# mother_board_PLA_4.net
KiCad netlist of a schematic drawn in EAGLE
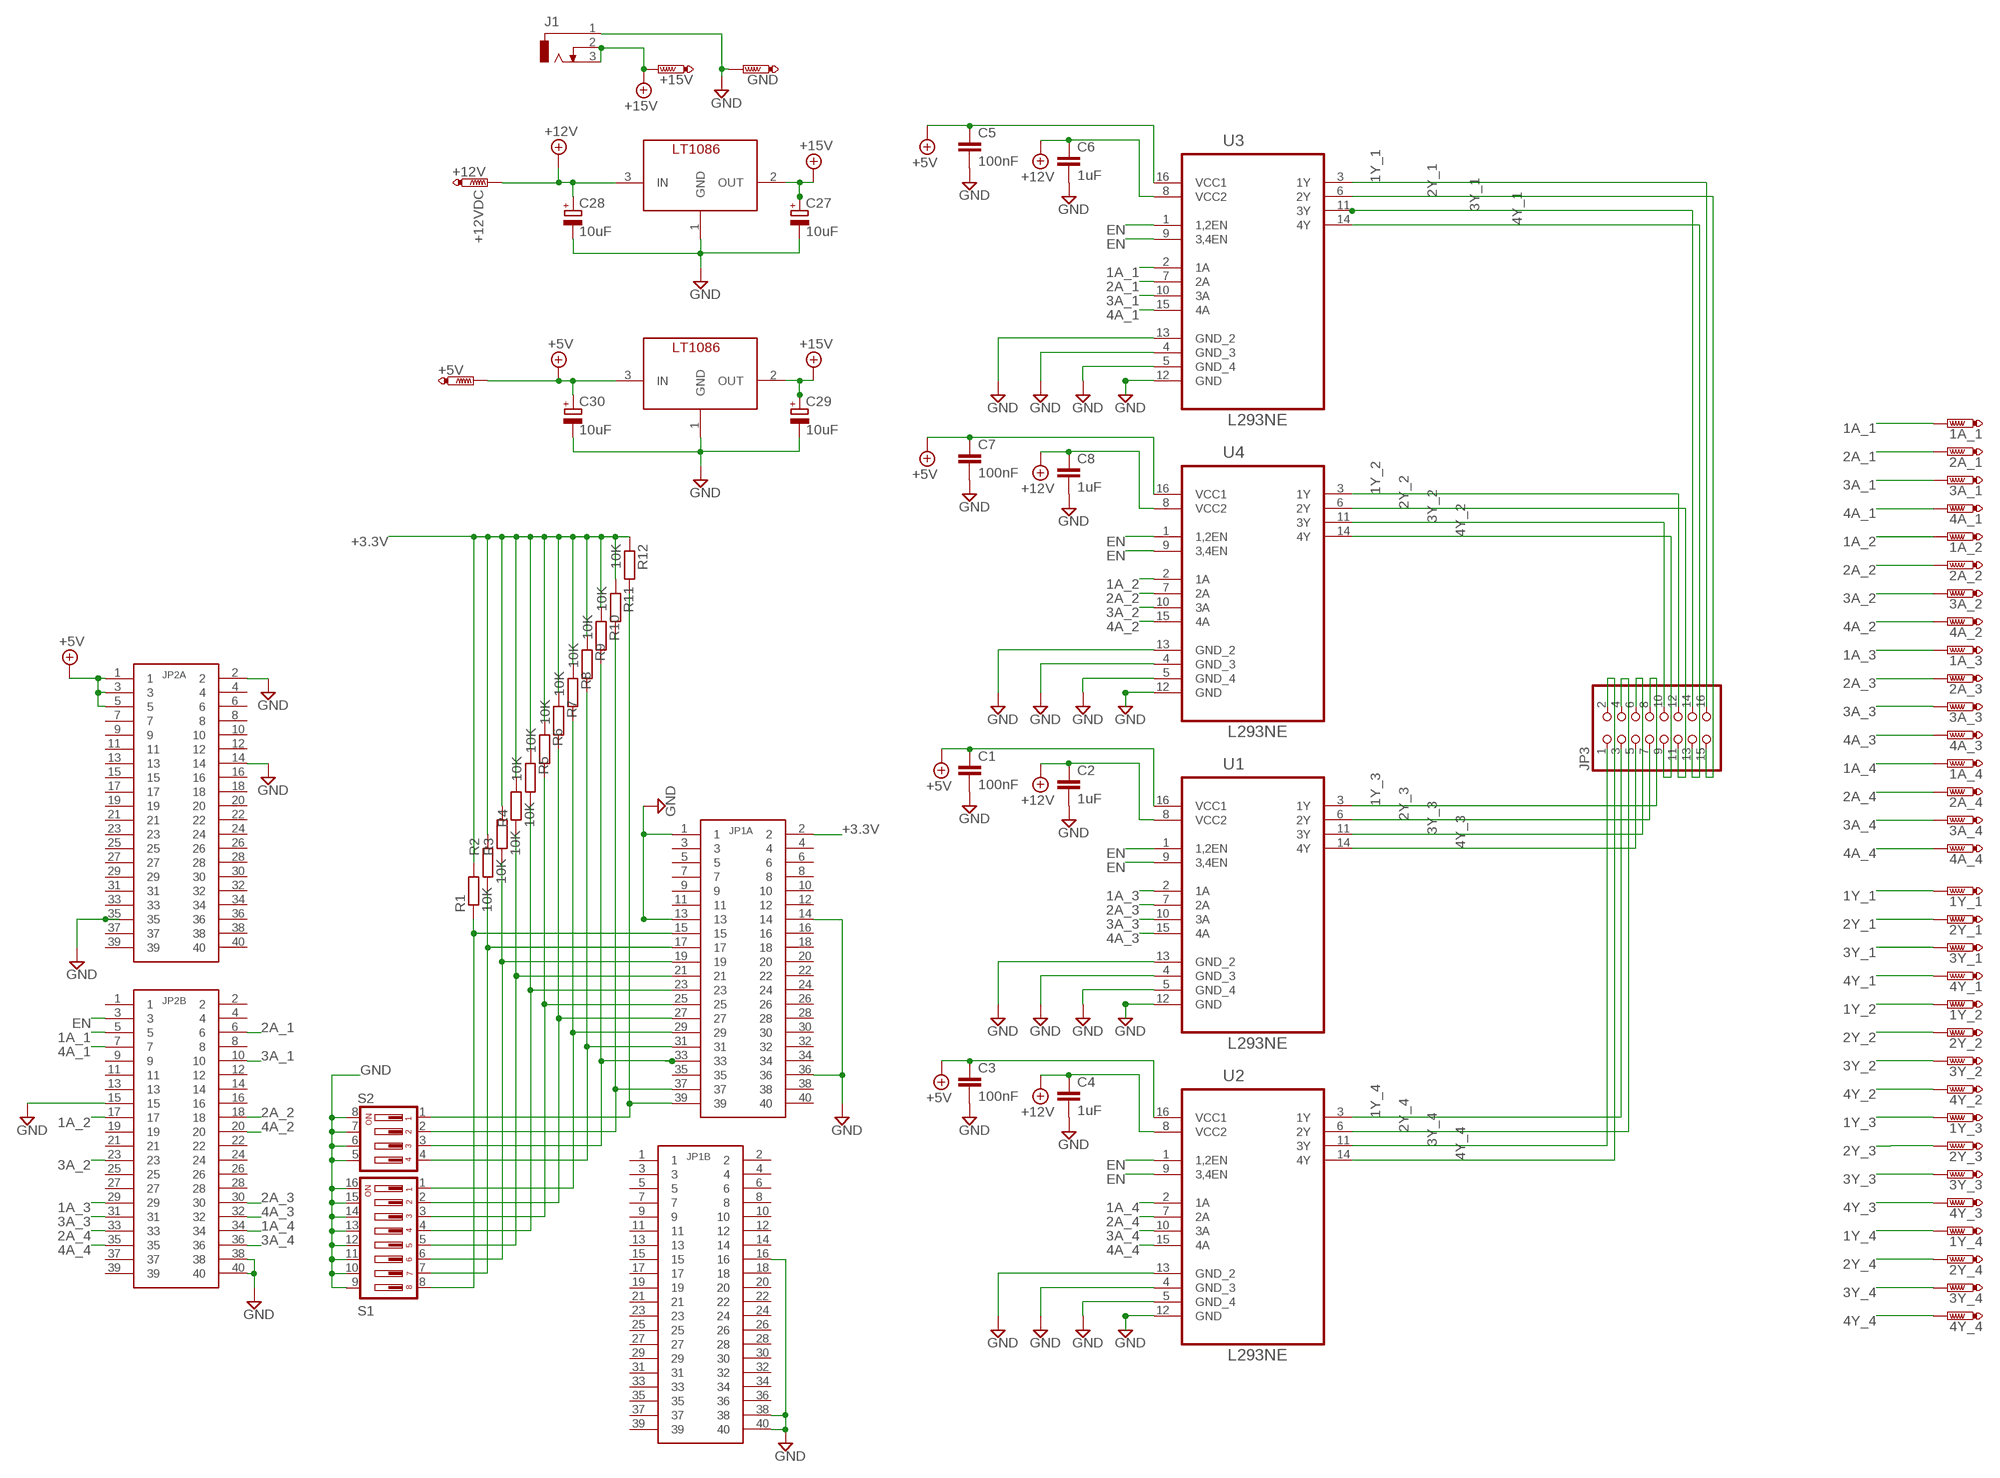
[diagram p0: schematic, sheet 1]

(export (version "E")
  (design (tool "Eeschema 10.0.6"))
  (components
    (comp (ref "+5V")
      (value "PTR1PAD1-20Y")
      (footprint "eagle-import:P1-20Y")
      (fields (field (name "SPICEPREFIX") "X"))
      (libsource (lib "eagle-import") (part "PTR1PAD1-20Y"))
    )
    (comp (ref "+12V")
      (value "PTR1PAD1-20Y")
      (footprint "eagle-import:P1-20Y")
      (fields (field (name "SPICEPREFIX") "X") (field (name "TP_SIGNAL_NAME") "+12VDC"))
      (libsource (lib "eagle-import") (part "PTR1PAD1-20Y"))
    )
    (comp (ref "+15V")
      (value "PTR1PAD1-20Y")
      (footprint "eagle-import:P1-20Y")
      (fields (field (name "SPICEPREFIX") "X"))
      (libsource (lib "eagle-import") (part "PTR1PAD1-20Y"))
    )
    (comp (ref "1A_1")
      (value "PTR1PAD1-20Y")
      (footprint "eagle-import:P1-20Y")
      (fields (field (name "SPICEPREFIX") "X"))
      (libsource (lib "eagle-import") (part "PTR1PAD1-20Y"))
    )
    (comp (ref "1A_2")
      (value "PTR1PAD1-20Y")
      (footprint "eagle-import:P1-20Y")
      (fields (field (name "SPICEPREFIX") "X"))
      (libsource (lib "eagle-import") (part "PTR1PAD1-20Y"))
    )
    (comp (ref "1A_3")
      (value "PTR1PAD1-20Y")
      (footprint "eagle-import:P1-20Y")
      (fields (field (name "SPICEPREFIX") "X"))
      (libsource (lib "eagle-import") (part "PTR1PAD1-20Y"))
    )
    (comp (ref "1A_4")
      (value "PTR1PAD1-20Y")
      (footprint "eagle-import:P1-20Y")
      (fields (field (name "SPICEPREFIX") "X"))
      (libsource (lib "eagle-import") (part "PTR1PAD1-20Y"))
    )
    (comp (ref "1Y_1")
      (value "PTR1PAD1-20Y")
      (footprint "eagle-import:P1-20Y")
      (fields (field (name "SPICEPREFIX") "X"))
      (libsource (lib "eagle-import") (part "PTR1PAD1-20Y"))
    )
    (comp (ref "1Y_2")
      (value "PTR1PAD1-20Y")
      (footprint "eagle-import:P1-20Y")
      (fields (field (name "SPICEPREFIX") "X"))
      (libsource (lib "eagle-import") (part "PTR1PAD1-20Y"))
    )
    (comp (ref "1Y_3")
      (value "PTR1PAD1-20Y")
      (footprint "eagle-import:P1-20Y")
      (fields (field (name "SPICEPREFIX") "X"))
      (libsource (lib "eagle-import") (part "PTR1PAD1-20Y"))
    )
    (comp (ref "1Y_4")
      (value "PTR1PAD1-20Y")
      (footprint "eagle-import:P1-20Y")
      (fields (field (name "SPICEPREFIX") "X"))
      (libsource (lib "eagle-import") (part "PTR1PAD1-20Y"))
    )
    (comp (ref "2A_1")
      (value "PTR1PAD1-20Y")
      (footprint "eagle-import:P1-20Y")
      (fields (field (name "SPICEPREFIX") "X"))
      (libsource (lib "eagle-import") (part "PTR1PAD1-20Y"))
    )
    (comp (ref "2A_2")
      (value "PTR1PAD1-20Y")
      (footprint "eagle-import:P1-20Y")
      (fields (field (name "SPICEPREFIX") "X"))
      (libsource (lib "eagle-import") (part "PTR1PAD1-20Y"))
    )
    (comp (ref "2A_3")
      (value "PTR1PAD1-20Y")
      (footprint "eagle-import:P1-20Y")
      (fields (field (name "SPICEPREFIX") "X"))
      (libsource (lib "eagle-import") (part "PTR1PAD1-20Y"))
    )
    (comp (ref "2A_4")
      (value "PTR1PAD1-20Y")
      (footprint "eagle-import:P1-20Y")
      (fields (field (name "SPICEPREFIX") "X"))
      (libsource (lib "eagle-import") (part "PTR1PAD1-20Y"))
    )
    (comp (ref "2Y_1")
      (value "PTR1PAD1-20Y")
      (footprint "eagle-import:P1-20Y")
      (fields (field (name "SPICEPREFIX") "X"))
      (libsource (lib "eagle-import") (part "PTR1PAD1-20Y"))
    )
    (comp (ref "2Y_2")
      (value "PTR1PAD1-20Y")
      (footprint "eagle-import:P1-20Y")
      (fields (field (name "SPICEPREFIX") "X"))
      (libsource (lib "eagle-import") (part "PTR1PAD1-20Y"))
    )
    (comp (ref "2Y_3")
      (value "PTR1PAD1-20Y")
      (footprint "eagle-import:P1-20Y")
      (fields (field (name "SPICEPREFIX") "X"))
      (libsource (lib "eagle-import") (part "PTR1PAD1-20Y"))
    )
    (comp (ref "2Y_4")
      (value "PTR1PAD1-20Y")
      (footprint "eagle-import:P1-20Y")
      (fields (field (name "SPICEPREFIX") "X"))
      (libsource (lib "eagle-import") (part "PTR1PAD1-20Y"))
    )
    (comp (ref "3A_1")
      (value "PTR1PAD1-20Y")
      (footprint "eagle-import:P1-20Y")
      (fields (field (name "SPICEPREFIX") "X"))
      (libsource (lib "eagle-import") (part "PTR1PAD1-20Y"))
    )
    (comp (ref "3A_2")
      (value "PTR1PAD1-20Y")
      (footprint "eagle-import:P1-20Y")
      (fields (field (name "SPICEPREFIX") "X"))
      (libsource (lib "eagle-import") (part "PTR1PAD1-20Y"))
    )
    (comp (ref "3A_3")
      (value "PTR1PAD1-20Y")
      (footprint "eagle-import:P1-20Y")
      (fields (field (name "SPICEPREFIX") "X"))
      (libsource (lib "eagle-import") (part "PTR1PAD1-20Y"))
    )
    (comp (ref "3A_4")
      (value "PTR1PAD1-20Y")
      (footprint "eagle-import:P1-20Y")
      (fields (field (name "SPICEPREFIX") "X"))
      (libsource (lib "eagle-import") (part "PTR1PAD1-20Y"))
    )
    (comp (ref "3Y_1")
      (value "PTR1PAD1-20Y")
      (footprint "eagle-import:P1-20Y")
      (fields (field (name "SPICEPREFIX") "X"))
      (libsource (lib "eagle-import") (part "PTR1PAD1-20Y"))
    )
    (comp (ref "3Y_2")
      (value "PTR1PAD1-20Y")
      (footprint "eagle-import:P1-20Y")
      (fields (field (name "SPICEPREFIX") "X"))
      (libsource (lib "eagle-import") (part "PTR1PAD1-20Y"))
    )
    (comp (ref "3Y_3")
      (value "PTR1PAD1-20Y")
      (footprint "eagle-import:P1-20Y")
      (fields (field (name "SPICEPREFIX") "X"))
      (libsource (lib "eagle-import") (part "PTR1PAD1-20Y"))
    )
    (comp (ref "3Y_4")
      (value "PTR1PAD1-20Y")
      (footprint "eagle-import:P1-20Y")
      (fields (field (name "SPICEPREFIX") "X"))
      (libsource (lib "eagle-import") (part "PTR1PAD1-20Y"))
    )
    (comp (ref "4A_1")
      (value "PTR1PAD1-20Y")
      (footprint "eagle-import:P1-20Y")
      (fields (field (name "SPICEPREFIX") "X"))
      (libsource (lib "eagle-import") (part "PTR1PAD1-20Y"))
    )
    (comp (ref "4A_2")
      (value "PTR1PAD1-20Y")
      (footprint "eagle-import:P1-20Y")
      (fields (field (name "SPICEPREFIX") "X"))
      (libsource (lib "eagle-import") (part "PTR1PAD1-20Y"))
    )
    (comp (ref "4A_3")
      (value "PTR1PAD1-20Y")
      (footprint "eagle-import:P1-20Y")
      (fields (field (name "SPICEPREFIX") "X"))
      (libsource (lib "eagle-import") (part "PTR1PAD1-20Y"))
    )
    (comp (ref "4A_4")
      (value "PTR1PAD1-20Y")
      (footprint "eagle-import:P1-20Y")
      (fields (field (name "SPICEPREFIX") "X"))
      (libsource (lib "eagle-import") (part "PTR1PAD1-20Y"))
    )
    (comp (ref "4Y_1")
      (value "PTR1PAD1-20Y")
      (footprint "eagle-import:P1-20Y")
      (fields (field (name "SPICEPREFIX") "X"))
      (libsource (lib "eagle-import") (part "PTR1PAD1-20Y"))
    )
    (comp (ref "4Y_2")
      (value "PTR1PAD1-20Y")
      (footprint "eagle-import:P1-20Y")
      (fields (field (name "SPICEPREFIX") "X"))
      (libsource (lib "eagle-import") (part "PTR1PAD1-20Y"))
    )
    (comp (ref "4Y_3")
      (value "PTR1PAD1-20Y")
      (footprint "eagle-import:P1-20Y")
      (fields (field (name "SPICEPREFIX") "X"))
      (libsource (lib "eagle-import") (part "PTR1PAD1-20Y"))
    )
    (comp (ref "4Y_4")
      (value "PTR1PAD1-20Y")
      (footprint "eagle-import:P1-20Y")
      (fields (field (name "SPICEPREFIX") "X"))
      (libsource (lib "eagle-import") (part "PTR1PAD1-20Y"))
    )
    (comp (ref "C1")
      (value "100nF")
      (footprint "eagle-import:C050-030X075")
      (libsource (lib "eagle-import") (part "C-EU050-030X075"))
    )
    (comp (ref "C2")
      (value "1uF")
      (footprint "eagle-import:C050-030X075")
      (libsource (lib "eagle-import") (part "C-EU050-030X075"))
    )
    (comp (ref "C3")
      (value "100nF")
      (footprint "eagle-import:C050-030X075")
      (libsource (lib "eagle-import") (part "C-EU050-030X075"))
    )
    (comp (ref "C4")
      (value "1uF")
      (footprint "eagle-import:C050-030X075")
      (libsource (lib "eagle-import") (part "C-EU050-030X075"))
    )
    (comp (ref "C5")
      (value "100nF")
      (footprint "eagle-import:C050-030X075")
      (libsource (lib "eagle-import") (part "C-EU050-030X075"))
    )
    (comp (ref "C6")
      (value "1uF")
      (footprint "eagle-import:C050-030X075")
      (libsource (lib "eagle-import") (part "C-EU050-030X075"))
    )
    (comp (ref "C7")
      (value "100nF")
      (footprint "eagle-import:C050-030X075")
      (fields (field (name "SPICEPREFIX") "100n"))
      (libsource (lib "eagle-import") (part "C-EU050-030X075"))
    )
    (comp (ref "C8")
      (value "1uF")
      (footprint "eagle-import:C050-030X075")
      (fields (field (name "SPICEPREFIX") "1uF"))
      (libsource (lib "eagle-import") (part "C-EU050-030X075"))
    )
    (comp (ref "C27")
      (value "10uF")
      (footprint "eagle-import:E5-10,5")
      (libsource (lib "eagle-import") (part "CPOL-EUE5-10.5"))
    )
    (comp (ref "C28")
      (value "10uF")
      (footprint "eagle-import:E5-10,5")
      (libsource (lib "eagle-import") (part "CPOL-EUE5-10.5"))
    )
    (comp (ref "C29")
      (value "10uF")
      (footprint "eagle-import:E5-10,5")
      (libsource (lib "eagle-import") (part "CPOL-EUE5-10.5"))
    )
    (comp (ref "C30")
      (value "10uF")
      (footprint "eagle-import:E5-10,5")
      (libsource (lib "eagle-import") (part "CPOL-EUE5-10.5"))
    )
    (comp (ref "GND")
      (value "PTR1PAD1-20Y")
      (footprint "eagle-import:P1-20Y")
      (fields (field (name "SPICEPREFIX") "X"))
      (libsource (lib "eagle-import") (part "PTR1PAD1-20Y"))
    )
    (comp (ref "J1")
      (value "DCJ0303")
      (footprint "eagle-import:DCJ0303")
      (libsource (lib "eagle-import") (part "DCJ0303"))
    )
    (comp (ref "JP1A")
      (value "PIN_HEADER_2MM")
      (footprint "eagle-import:PIN_HEADER_2MM")
      (libsource (lib "eagle-import") (part "PIN_HEADER_2MM"))
    )
    (comp (ref "JP1B")
      (value "PIN_HEADER_2MM")
      (footprint "eagle-import:PIN_HEADER_2MM")
      (libsource (lib "eagle-import") (part "PIN_HEADER_2MM"))
    )
    (comp (ref "JP2A")
      (value "PIN_HEADER_2MM")
      (footprint "eagle-import:PIN_HEADER_2MM")
      (libsource (lib "eagle-import") (part "PIN_HEADER_2MM"))
    )
    (comp (ref "JP2B")
      (value "PIN_HEADER_2MM")
      (footprint "eagle-import:PIN_HEADER_2MM")
      (libsource (lib "eagle-import") (part "PIN_HEADER_2MM"))
    )
    (comp (ref "JP3")
      (value "PINHD-2X8")
      (footprint "eagle-import:2X08")
      (libsource (lib "eagle-import") (part "PINHD-2X8"))
    )
    (comp (ref "R1")
      (value "10K")
      (footprint "eagle-import:0207_10")
      (libsource (lib "eagle-import") (part "R-EU_0207/10"))
    )
    (comp (ref "R2")
      (value "10K")
      (footprint "eagle-import:0207_10")
      (libsource (lib "eagle-import") (part "R-EU_0207/10"))
    )
    (comp (ref "R3")
      (value "10K")
      (footprint "eagle-import:0207_10")
      (libsource (lib "eagle-import") (part "R-EU_0207/10"))
    )
    (comp (ref "R4")
      (value "10K")
      (footprint "eagle-import:0207_10")
      (libsource (lib "eagle-import") (part "R-EU_0207/10"))
    )
    (comp (ref "R5")
      (value "10K")
      (footprint "eagle-import:0207_10")
      (libsource (lib "eagle-import") (part "R-EU_0207/10"))
    )
    (comp (ref "R6")
      (value "10K")
      (footprint "eagle-import:0207_10")
      (libsource (lib "eagle-import") (part "R-EU_0207/10"))
    )
    (comp (ref "R7")
      (value "10K")
      (footprint "eagle-import:0207_10")
      (libsource (lib "eagle-import") (part "R-EU_0207/10"))
    )
    (comp (ref "R8")
      (value "10K")
      (footprint "eagle-import:0207_10")
      (libsource (lib "eagle-import") (part "R-EU_0207/10"))
    )
    (comp (ref "R9")
      (value "10K")
      (footprint "eagle-import:0207_10")
      (libsource (lib "eagle-import") (part "R-EU_0207/10"))
    )
    (comp (ref "R10")
      (value "10K")
      (footprint "eagle-import:0207_10")
      (libsource (lib "eagle-import") (part "R-EU_0207/10"))
    )
    (comp (ref "R11")
      (value "10K")
      (footprint "eagle-import:0207_10")
      (libsource (lib "eagle-import") (part "R-EU_0207/10"))
    )
    (comp (ref "R12")
      (value "10K")
      (footprint "eagle-import:0207_10")
      (libsource (lib "eagle-import") (part "R-EU_0207/10"))
    )
    (comp (ref "S1")
      (value "DIP04YL")
      (footprint "eagle-import:DIP04YL")
      (libsource (lib "eagle-import") (part "DIP04YL"))
    )
    (comp (ref "S2")
      (value "DIP08YL")
      (footprint "eagle-import:DIP08YL")
      (libsource (lib "eagle-import") (part "DIP08YL"))
    )
    (comp (ref "U$4")
      (value "LT1086LT1086-V")
      (footprint "eagle-import:TO220_VERTICAL")
      (libsource (lib "eagle-import") (part "LT1086LT1086-V"))
    )
    (comp (ref "U$6")
      (value "LT1086LT1086-V")
      (footprint "eagle-import:TO220_VERTICAL")
      (libsource (lib "eagle-import") (part "LT1086LT1086-V"))
    )
    (comp (ref "U1")
      (value "L293NE")
      (footprint "eagle-import:DIP254P762X508-16")
      (libsource (lib "eagle-import") (part "L293NE"))
    )
    (comp (ref "U2")
      (value "L293NE")
      (footprint "eagle-import:DIP254P762X508-16")
      (libsource (lib "eagle-import") (part "L293NE"))
    )
    (comp (ref "U3")
      (value "L293NE")
      (footprint "eagle-import:DIP254P762X508-16")
      (libsource (lib "eagle-import") (part "L293NE"))
    )
    (comp (ref "U4")
      (value "L293NE")
      (footprint "eagle-import:DIP254P762X508-16")
      (libsource (lib "eagle-import") (part "L293NE"))
    )
  )
  (nets
    (net (code "1") (name "+5V") (class "Default")
      (node (ref "+5V") (pin "TP") (pinfunction "TP_TP") (pintype "input"))
      (node (ref "C1") (pin "1") (pinfunction "1_1") (pintype "passive"))
      (node (ref "C3") (pin "1") (pinfunction "1_1") (pintype "passive"))
      (node (ref "C30") (pin "+") (pinfunction "+_+") (pintype "passive"))
      (node (ref "C5") (pin "1") (pinfunction "1_1") (pintype "passive"))
      (node (ref "C7") (pin "1") (pinfunction "1_1") (pintype "passive"))
      (node (ref "JP2A") (pin "1") (pinfunction "1_1") (pintype "bidirectional"))
      (node (ref "JP2A") (pin "3") (pinfunction "3_3") (pintype "bidirectional"))
      (node (ref "JP2A") (pin "5") (pinfunction "5_5") (pintype "bidirectional"))
      (node (ref "U$4") (pin "3") (pinfunction "IN_3") (pintype "bidirectional"))
      (node (ref "U1") (pin "16") (pinfunction "VCC1_16") (pintype "power_in"))
      (node (ref "U2") (pin "16") (pinfunction "VCC1_16") (pintype "power_in"))
      (node (ref "U3") (pin "16") (pinfunction "VCC1_16") (pintype "power_in"))
      (node (ref "U4") (pin "16") (pinfunction "VCC1_16") (pintype "power_in"))
    )
    (net (code "2") (name "+12V") (class "Default")
      (node (ref "+12V") (pin "TP") (pinfunction "TP_TP") (pintype "input"))
      (node (ref "C2") (pin "1") (pinfunction "1_1") (pintype "passive"))
      (node (ref "C28") (pin "+") (pinfunction "+_+") (pintype "passive"))
      (node (ref "C4") (pin "1") (pinfunction "1_1") (pintype "passive"))
      (node (ref "C6") (pin "1") (pinfunction "1_1") (pintype "passive"))
      (node (ref "C8") (pin "1") (pinfunction "1_1") (pintype "passive"))
      (node (ref "U$6") (pin "3") (pinfunction "IN_3") (pintype "bidirectional"))
      (node (ref "U1") (pin "8") (pinfunction "VCC2_8") (pintype "power_in"))
      (node (ref "U2") (pin "8") (pinfunction "VCC2_8") (pintype "power_in"))
      (node (ref "U3") (pin "8") (pinfunction "VCC2_8") (pintype "power_in"))
      (node (ref "U4") (pin "8") (pinfunction "VCC2_8") (pintype "power_in"))
    )
    (net (code "3") (name "+15V") (class "Default")
      (node (ref "+15V") (pin "TP") (pinfunction "TP_TP") (pintype "input"))
      (node (ref "C27") (pin "+") (pinfunction "+_+") (pintype "passive"))
      (node (ref "C29") (pin "+") (pinfunction "+_+") (pintype "passive"))
      (node (ref "J1") (pin "2") (pinfunction "2_2") (pintype "passive"))
      (node (ref "J1") (pin "3") (pinfunction "3_3") (pintype "passive"))
      (node (ref "U$4") (pin "2") (pinfunction "OUT_2") (pintype "bidirectional"))
      (node (ref "U$6") (pin "2") (pinfunction "OUT_2") (pintype "bidirectional"))
    )
    (net (code "4") (name "/+3.3V") (class "Default")
      (node (ref "JP1A") (pin "2") (pinfunction "2_2") (pintype "bidirectional"))
      (node (ref "R1") (pin "2") (pinfunction "2_2") (pintype "passive"))
      (node (ref "R10") (pin "1") (pinfunction "1_1") (pintype "passive"))
      (node (ref "R11") (pin "1") (pinfunction "1_1") (pintype "passive"))
      (node (ref "R12") (pin "1") (pinfunction "1_1") (pintype "passive"))
      (node (ref "R2") (pin "2") (pinfunction "2_2") (pintype "passive"))
      (node (ref "R3") (pin "2") (pinfunction "2_2") (pintype "passive"))
      (node (ref "R4") (pin "2") (pinfunction "2_2") (pintype "passive"))
      (node (ref "R5") (pin "1") (pinfunction "1_1") (pintype "passive"))
      (node (ref "R6") (pin "1") (pinfunction "1_1") (pintype "passive"))
      (node (ref "R7") (pin "1") (pinfunction "1_1") (pintype "passive"))
      (node (ref "R8") (pin "1") (pinfunction "1_1") (pintype "passive"))
      (node (ref "R9") (pin "1") (pinfunction "1_1") (pintype "passive"))
    )
    (net (code "5") (name "/1A_1") (class "Default")
      (node (ref "1A_1") (pin "TP") (pinfunction "TP_TP") (pintype "input"))
      (node (ref "JP2B") (pin "5") (pinfunction "5_5") (pintype "bidirectional"))
      (node (ref "U3") (pin "2") (pinfunction "1A_2") (pintype "input"))
    )
    (net (code "6") (name "/1A_2") (class "Default")
      (node (ref "1A_2") (pin "TP") (pinfunction "TP_TP") (pintype "input"))
      (node (ref "JP2B") (pin "17") (pinfunction "17_17") (pintype "bidirectional"))
      (node (ref "U4") (pin "2") (pinfunction "1A_2") (pintype "input"))
    )
    (net (code "7") (name "/1A_3") (class "Default")
      (node (ref "1A_3") (pin "TP") (pinfunction "TP_TP") (pintype "input"))
      (node (ref "JP2B") (pin "29") (pinfunction "29_29") (pintype "bidirectional"))
      (node (ref "U1") (pin "2") (pinfunction "1A_2") (pintype "input"))
    )
    (net (code "8") (name "/1A_4") (class "Default")
      (node (ref "1A_4") (pin "TP") (pinfunction "TP_TP") (pintype "input"))
      (node (ref "JP2B") (pin "34") (pinfunction "34_34") (pintype "bidirectional"))
      (node (ref "U2") (pin "2") (pinfunction "1A_2") (pintype "input"))
    )
    (net (code "9") (name "/1Y_1") (class "Default")
      (node (ref "1Y_1") (pin "TP") (pinfunction "TP_TP") (pintype "input"))
      (node (ref "JP3") (pin "16") (pinfunction "16_16") (pintype "passive"))
      (node (ref "U3") (pin "3") (pinfunction "1Y_3") (pintype "output"))
    )
    (net (code "10") (name "/1Y_2") (class "Default")
      (node (ref "1Y_2") (pin "TP") (pinfunction "TP_TP") (pintype "input"))
      (node (ref "JP3") (pin "12") (pinfunction "12_12") (pintype "passive"))
      (node (ref "U4") (pin "3") (pinfunction "1Y_3") (pintype "output"))
    )
    (net (code "11") (name "/1Y_3") (class "Default")
      (node (ref "1Y_3") (pin "TP") (pinfunction "TP_TP") (pintype "input"))
      (node (ref "JP3") (pin "8") (pinfunction "8_8") (pintype "passive"))
      (node (ref "U1") (pin "3") (pinfunction "1Y_3") (pintype "output"))
    )
    (net (code "12") (name "/1Y_4") (class "Default")
      (node (ref "1Y_4") (pin "TP") (pinfunction "TP_TP") (pintype "input"))
      (node (ref "JP3") (pin "3") (pinfunction "3_3") (pintype "passive"))
      (node (ref "U2") (pin "3") (pinfunction "1Y_3") (pintype "output"))
    )
    (net (code "13") (name "/2A_1") (class "Default")
      (node (ref "2A_1") (pin "TP") (pinfunction "TP_TP") (pintype "input"))
      (node (ref "JP2B") (pin "6") (pinfunction "6_6") (pintype "bidirectional"))
      (node (ref "U3") (pin "7") (pinfunction "2A_7") (pintype "input"))
    )
    (net (code "14") (name "/2A_2") (class "Default")
      (node (ref "2A_2") (pin "TP") (pinfunction "TP_TP") (pintype "input"))
      (node (ref "JP2B") (pin "18") (pinfunction "18_18") (pintype "bidirectional"))
      (node (ref "U4") (pin "7") (pinfunction "2A_7") (pintype "input"))
    )
    (net (code "15") (name "/2A_3") (class "Default")
      (node (ref "2A_3") (pin "TP") (pinfunction "TP_TP") (pintype "input"))
      (node (ref "JP2B") (pin "30") (pinfunction "30_30") (pintype "bidirectional"))
      (node (ref "U1") (pin "7") (pinfunction "2A_7") (pintype "input"))
    )
    (net (code "16") (name "/2A_4") (class "Default")
      (node (ref "2A_4") (pin "TP") (pinfunction "TP_TP") (pintype "input"))
      (node (ref "JP2B") (pin "33") (pinfunction "33_33") (pintype "bidirectional"))
      (node (ref "U2") (pin "7") (pinfunction "2A_7") (pintype "input"))
    )
    (net (code "17") (name "/2Y_1") (class "Default")
      (node (ref "2Y_1") (pin "TP") (pinfunction "TP_TP") (pintype "input"))
      (node (ref "JP3") (pin "15") (pinfunction "15_15") (pintype "passive"))
      (node (ref "U3") (pin "6") (pinfunction "2Y_6") (pintype "output"))
    )
    (net (code "18") (name "/2Y_2") (class "Default")
      (node (ref "2Y_2") (pin "TP") (pinfunction "TP_TP") (pintype "input"))
      (node (ref "JP3") (pin "11") (pinfunction "11_11") (pintype "passive"))
      (node (ref "U4") (pin "6") (pinfunction "2Y_6") (pintype "output"))
    )
    (net (code "19") (name "/2Y_3") (class "Default")
      (node (ref "2Y_3") (pin "TP") (pinfunction "TP_TP") (pintype "input"))
      (node (ref "JP3") (pin "7") (pinfunction "7_7") (pintype "passive"))
      (node (ref "U1") (pin "6") (pinfunction "2Y_6") (pintype "output"))
    )
    (net (code "20") (name "/2Y_4") (class "Default")
      (node (ref "2Y_4") (pin "TP") (pinfunction "TP_TP") (pintype "input"))
      (node (ref "JP3") (pin "4") (pinfunction "4_4") (pintype "passive"))
      (node (ref "U2") (pin "6") (pinfunction "2Y_6") (pintype "output"))
    )
    (net (code "21") (name "/3A_1") (class "Default")
      (node (ref "3A_1") (pin "TP") (pinfunction "TP_TP") (pintype "input"))
      (node (ref "JP2B") (pin "10") (pinfunction "10_10") (pintype "bidirectional"))
      (node (ref "U3") (pin "10") (pinfunction "3A_10") (pintype "input"))
    )
    (net (code "22") (name "/3A_2") (class "Default")
      (node (ref "3A_2") (pin "TP") (pinfunction "TP_TP") (pintype "input"))
      (node (ref "JP2B") (pin "23") (pinfunction "23_23") (pintype "bidirectional"))
      (node (ref "U4") (pin "10") (pinfunction "3A_10") (pintype "input"))
    )
    (net (code "23") (name "/3A_3") (class "Default")
      (node (ref "3A_3") (pin "TP") (pinfunction "TP_TP") (pintype "input"))
      (node (ref "JP2B") (pin "31") (pinfunction "31_31") (pintype "bidirectional"))
      (node (ref "U1") (pin "10") (pinfunction "3A_10") (pintype "input"))
    )
    (net (code "24") (name "/3A_4") (class "Default")
      (node (ref "3A_4") (pin "TP") (pinfunction "TP_TP") (pintype "input"))
      (node (ref "JP2B") (pin "36") (pinfunction "36_36") (pintype "bidirectional"))
      (node (ref "U2") (pin "10") (pinfunction "3A_10") (pintype "input"))
    )
    (net (code "25") (name "/3Y_1") (class "Default")
      (node (ref "3Y_1") (pin "TP") (pinfunction "TP_TP") (pintype "input"))
      (node (ref "JP3") (pin "14") (pinfunction "14_14") (pintype "passive"))
      (node (ref "U3") (pin "11") (pinfunction "3Y_11") (pintype "output"))
    )
    (net (code "26") (name "/3Y_2") (class "Default")
      (node (ref "3Y_2") (pin "TP") (pinfunction "TP_TP") (pintype "input"))
      (node (ref "JP3") (pin "10") (pinfunction "10_10") (pintype "passive"))
      (node (ref "U4") (pin "11") (pinfunction "3Y_11") (pintype "output"))
    )
    (net (code "27") (name "/3Y_3") (class "Default")
      (node (ref "3Y_3") (pin "TP") (pinfunction "TP_TP") (pintype "input"))
      (node (ref "JP3") (pin "6") (pinfunction "6_6") (pintype "passive"))
      (node (ref "U1") (pin "11") (pinfunction "3Y_11") (pintype "output"))
    )
    (net (code "28") (name "/3Y_4") (class "Default")
      (node (ref "3Y_4") (pin "TP") (pinfunction "TP_TP") (pintype "input"))
      (node (ref "JP3") (pin "1") (pinfunction "1_1") (pintype "passive"))
      (node (ref "U2") (pin "11") (pinfunction "3Y_11") (pintype "output"))
    )
    (net (code "29") (name "/4A_1") (class "Default")
      (node (ref "4A_1") (pin "TP") (pinfunction "TP_TP") (pintype "input"))
      (node (ref "JP2B") (pin "7") (pinfunction "7_7") (pintype "bidirectional"))
      (node (ref "U3") (pin "15") (pinfunction "4A_15") (pintype "input"))
    )
    (net (code "30") (name "/4A_2") (class "Default")
      (node (ref "4A_2") (pin "TP") (pinfunction "TP_TP") (pintype "input"))
      (node (ref "JP2B") (pin "20") (pinfunction "20_20") (pintype "bidirectional"))
      (node (ref "U4") (pin "15") (pinfunction "4A_15") (pintype "input"))
    )
    (net (code "31") (name "/4A_3") (class "Default")
      (node (ref "4A_3") (pin "TP") (pinfunction "TP_TP") (pintype "input"))
      (node (ref "JP2B") (pin "32") (pinfunction "32_32") (pintype "bidirectional"))
      (node (ref "U1") (pin "15") (pinfunction "4A_15") (pintype "input"))
    )
    (net (code "32") (name "/4A_4") (class "Default")
      (node (ref "4A_4") (pin "TP") (pinfunction "TP_TP") (pintype "input"))
      (node (ref "JP2B") (pin "35") (pinfunction "35_35") (pintype "bidirectional"))
      (node (ref "U2") (pin "15") (pinfunction "4A_15") (pintype "input"))
    )
    (net (code "33") (name "/4Y_1") (class "Default")
      (node (ref "4Y_1") (pin "TP") (pinfunction "TP_TP") (pintype "input"))
      (node (ref "JP3") (pin "13") (pinfunction "13_13") (pintype "passive"))
      (node (ref "U3") (pin "14") (pinfunction "4Y_14") (pintype "output"))
    )
    (net (code "34") (name "/4Y_2") (class "Default")
      (node (ref "4Y_2") (pin "TP") (pinfunction "TP_TP") (pintype "input"))
      (node (ref "JP3") (pin "9") (pinfunction "9_9") (pintype "passive"))
      (node (ref "U4") (pin "14") (pinfunction "4Y_14") (pintype "output"))
    )
    (net (code "35") (name "/4Y_3") (class "Default")
      (node (ref "4Y_3") (pin "TP") (pinfunction "TP_TP") (pintype "input"))
      (node (ref "JP3") (pin "5") (pinfunction "5_5") (pintype "passive"))
      (node (ref "U1") (pin "14") (pinfunction "4Y_14") (pintype "output"))
    )
    (net (code "36") (name "/4Y_4") (class "Default")
      (node (ref "4Y_4") (pin "TP") (pinfunction "TP_TP") (pintype "input"))
      (node (ref "JP3") (pin "2") (pinfunction "2_2") (pintype "passive"))
      (node (ref "U2") (pin "14") (pinfunction "4Y_14") (pintype "output"))
    )
    (net (code "37") (name "/EN") (class "Default")
      (node (ref "JP2B") (pin "3") (pinfunction "3_3") (pintype "bidirectional"))
      (node (ref "U1") (pin "1") (pinfunction "1,2EN_1") (pintype "input"))
      (node (ref "U1") (pin "9") (pinfunction "3,4EN_9") (pintype "input"))
      (node (ref "U2") (pin "1") (pinfunction "1,2EN_1") (pintype "input"))
      (node (ref "U2") (pin "9") (pinfunction "3,4EN_9") (pintype "input"))
      (node (ref "U3") (pin "1") (pinfunction "1,2EN_1") (pintype "input"))
      (node (ref "U3") (pin "9") (pinfunction "3,4EN_9") (pintype "input"))
      (node (ref "U4") (pin "1") (pinfunction "1,2EN_1") (pintype "input"))
      (node (ref "U4") (pin "9") (pinfunction "3,4EN_9") (pintype "input"))
    )
    (net (code "38") (name "GND") (class "Default")
      (node (ref "C1") (pin "2") (pinfunction "2_2") (pintype "passive"))
      (node (ref "C2") (pin "2") (pinfunction "2_2") (pintype "passive"))
      (node (ref "C27") (pin "-") (pinfunction "-_-") (pintype "passive"))
      (node (ref "C28") (pin "-") (pinfunction "-_-") (pintype "passive"))
      (node (ref "C29") (pin "-") (pinfunction "-_-") (pintype "passive"))
      (node (ref "C3") (pin "2") (pinfunction "2_2") (pintype "passive"))
      (node (ref "C30") (pin "-") (pinfunction "-_-") (pintype "passive"))
      (node (ref "C4") (pin "2") (pinfunction "2_2") (pintype "passive"))
      (node (ref "C5") (pin "2") (pinfunction "2_2") (pintype "passive"))
      (node (ref "C6") (pin "2") (pinfunction "2_2") (pintype "passive"))
      (node (ref "C7") (pin "2") (pinfunction "2_2") (pintype "passive"))
      (node (ref "C8") (pin "2") (pinfunction "2_2") (pintype "passive"))
      (node (ref "GND") (pin "TP") (pinfunction "TP_TP") (pintype "input"))
      (node (ref "J1") (pin "1") (pinfunction "1_1") (pintype "passive"))
      (node (ref "JP1A") (pin "1") (pinfunction "1_1") (pintype "bidirectional"))
      (node (ref "JP1A") (pin "13") (pinfunction "13_13") (pintype "bidirectional"))
      (node (ref "JP1A") (pin "14") (pinfunction "14_14") (pintype "bidirectional"))
      (node (ref "JP1A") (pin "36") (pinfunction "36_36") (pintype "bidirectional"))
      (node (ref "JP1B") (pin "16") (pinfunction "16_16") (pintype "bidirectional"))
      (node (ref "JP1B") (pin "38") (pinfunction "38_38") (pintype "bidirectional"))
      (node (ref "JP1B") (pin "40") (pinfunction "40_40") (pintype "bidirectional"))
      (node (ref "JP2A") (pin "14") (pinfunction "14_14") (pintype "bidirectional"))
      (node (ref "JP2A") (pin "2") (pinfunction "2_2") (pintype "bidirectional"))
      (node (ref "JP2A") (pin "35") (pinfunction "35_35") (pintype "bidirectional"))
      (node (ref "JP2B") (pin "15") (pinfunction "15_15") (pintype "bidirectional"))
      (node (ref "JP2B") (pin "38") (pinfunction "38_38") (pintype "bidirectional"))
      (node (ref "JP2B") (pin "40") (pinfunction "40_40") (pintype "bidirectional"))
      (node (ref "S1") (pin "5") (pinfunction "5_5") (pintype "passive"))
      (node (ref "S1") (pin "6") (pinfunction "6_6") (pintype "passive"))
      (node (ref "S1") (pin "7") (pinfunction "7_7") (pintype "passive"))
      (node (ref "S1") (pin "8") (pinfunction "8_8") (pintype "passive"))
      (node (ref "S2") (pin "10") (pinfunction "10_10") (pintype "passive"))
      (node (ref "S2") (pin "11") (pinfunction "11_11") (pintype "passive"))
      (node (ref "S2") (pin "12") (pinfunction "12_12") (pintype "passive"))
      (node (ref "S2") (pin "13") (pinfunction "13_13") (pintype "passive"))
      (node (ref "S2") (pin "14") (pinfunction "14_14") (pintype "passive"))
      (node (ref "S2") (pin "15") (pinfunction "15_15") (pintype "passive"))
      (node (ref "S2") (pin "16") (pinfunction "16_16") (pintype "passive"))
      (node (ref "S2") (pin "9") (pinfunction "9_9") (pintype "passive"))
      (node (ref "U$4") (pin "1") (pinfunction "GND_1") (pintype "bidirectional"))
      (node (ref "U$6") (pin "1") (pinfunction "GND_1") (pintype "bidirectional"))
      (node (ref "U1") (pin "12") (pinfunction "GND_12") (pintype "passive"))
      (node (ref "U1") (pin "13") (pinfunction "GND_2_13") (pintype "passive"))
      (node (ref "U1") (pin "4") (pinfunction "GND_3_4") (pintype "passive"))
      (node (ref "U1") (pin "5") (pinfunction "GND_4_5") (pintype "passive"))
      (node (ref "U2") (pin "12") (pinfunction "GND_12") (pintype "passive"))
      (node (ref "U2") (pin "13") (pinfunction "GND_2_13") (pintype "passive"))
      (node (ref "U2") (pin "4") (pinfunction "GND_3_4") (pintype "passive"))
      (node (ref "U2") (pin "5") (pinfunction "GND_4_5") (pintype "passive"))
      (node (ref "U3") (pin "12") (pinfunction "GND_12") (pintype "passive"))
      (node (ref "U3") (pin "13") (pinfunction "GND_2_13") (pintype "passive"))
      (node (ref "U3") (pin "4") (pinfunction "GND_3_4") (pintype "passive"))
      (node (ref "U3") (pin "5") (pinfunction "GND_4_5") (pintype "passive"))
      (node (ref "U4") (pin "12") (pinfunction "GND_12") (pintype "passive"))
      (node (ref "U4") (pin "13") (pinfunction "GND_2_13") (pintype "passive"))
      (node (ref "U4") (pin "4") (pinfunction "GND_3_4") (pintype "passive"))
      (node (ref "U4") (pin "5") (pinfunction "GND_4_5") (pintype "passive"))
    )
    (net (code "39") (name "Net-(JP1A-Pad15)") (class "Default")
      (node (ref "JP1A") (pin "15") (pinfunction "15_15") (pintype "bidirectional"))
      (node (ref "R1") (pin "1") (pinfunction "1_1") (pintype "passive"))
      (node (ref "S2") (pin "8") (pinfunction "8_8") (pintype "passive"))
    )
    (net (code "40") (name "Net-(JP1A-Pad17)") (class "Default")
      (node (ref "JP1A") (pin "17") (pinfunction "17_17") (pintype "bidirectional"))
      (node (ref "R2") (pin "1") (pinfunction "1_1") (pintype "passive"))
      (node (ref "S2") (pin "7") (pinfunction "7_7") (pintype "passive"))
    )
    (net (code "41") (name "Net-(JP1A-Pad19)") (class "Default")
      (node (ref "JP1A") (pin "19") (pinfunction "19_19") (pintype "bidirectional"))
      (node (ref "R3") (pin "1") (pinfunction "1_1") (pintype "passive"))
      (node (ref "S2") (pin "6") (pinfunction "6_6") (pintype "passive"))
    )
    (net (code "42") (name "Net-(JP1A-Pad21)") (class "Default")
      (node (ref "JP1A") (pin "21") (pinfunction "21_21") (pintype "bidirectional"))
      (node (ref "R4") (pin "1") (pinfunction "1_1") (pintype "passive"))
      (node (ref "S2") (pin "5") (pinfunction "5_5") (pintype "passive"))
    )
    (net (code "43") (name "Net-(JP1A-Pad23)") (class "Default")
      (node (ref "JP1A") (pin "23") (pinfunction "23_23") (pintype "bidirectional"))
      (node (ref "R5") (pin "2") (pinfunction "2_2") (pintype "passive"))
      (node (ref "S2") (pin "4") (pinfunction "4_4") (pintype "passive"))
    )
    (net (code "44") (name "Net-(JP1A-Pad25)") (class "Default")
      (node (ref "JP1A") (pin "25") (pinfunction "25_25") (pintype "bidirectional"))
      (node (ref "R6") (pin "2") (pinfunction "2_2") (pintype "passive"))
      (node (ref "S2") (pin "3") (pinfunction "3_3") (pintype "passive"))
    )
    (net (code "45") (name "Net-(JP1A-Pad27)") (class "Default")
      (node (ref "JP1A") (pin "27") (pinfunction "27_27") (pintype "bidirectional"))
      (node (ref "R7") (pin "2") (pinfunction "2_2") (pintype "passive"))
      (node (ref "S2") (pin "2") (pinfunction "2_2") (pintype "passive"))
    )
    (net (code "46") (name "Net-(JP1A-Pad29)") (class "Default")
      (node (ref "JP1A") (pin "29") (pinfunction "29_29") (pintype "bidirectional"))
      (node (ref "R8") (pin "2") (pinfunction "2_2") (pintype "passive"))
      (node (ref "S2") (pin "1") (pinfunction "1_1") (pintype "passive"))
    )
    (net (code "47") (name "Net-(JP1A-Pad31)") (class "Default")
      (node (ref "JP1A") (pin "31") (pinfunction "31_31") (pintype "bidirectional"))
      (node (ref "R9") (pin "2") (pinfunction "2_2") (pintype "passive"))
      (node (ref "S1") (pin "4") (pinfunction "4_4") (pintype "passive"))
    )
    (net (code "48") (name "Net-(JP1A-Pad33)") (class "Default")
      (node (ref "JP1A") (pin "33") (pinfunction "33_33") (pintype "bidirectional"))
      (node (ref "R10") (pin "2") (pinfunction "2_2") (pintype "passive"))
      (node (ref "S1") (pin "3") (pinfunction "3_3") (pintype "passive"))
    )
    (net (code "49") (name "Net-(JP1A-Pad37)") (class "Default")
      (node (ref "JP1A") (pin "37") (pinfunction "37_37") (pintype "bidirectional"))
      (node (ref "R11") (pin "2") (pinfunction "2_2") (pintype "passive"))
      (node (ref "S1") (pin "2") (pinfunction "2_2") (pintype "passive"))
    )
    (net (code "50") (name "Net-(JP1A-Pad39)") (class "Default")
      (node (ref "JP1A") (pin "39") (pinfunction "39_39") (pintype "bidirectional"))
      (node (ref "R12") (pin "2") (pinfunction "2_2") (pintype "passive"))
      (node (ref "S1") (pin "1") (pinfunction "1_1") (pintype "passive"))
    )
    (net (code "51") (name "unconnected-(JP1A-Pad3)") (class "Default")
      (node (ref "JP1A") (pin "3") (pinfunction "3_3") (pintype "bidirectional"))
    )
    (net (code "52") (name "unconnected-(JP1A-Pad4)") (class "Default")
      (node (ref "JP1A") (pin "4") (pinfunction "4_4") (pintype "bidirectional"))
    )
    (net (code "53") (name "unconnected-(JP1A-Pad5)") (class "Default")
      (node (ref "JP1A") (pin "5") (pinfunction "5_5") (pintype "bidirectional"))
    )
    (net (code "54") (name "unconnected-(JP1A-Pad6)") (class "Default")
      (node (ref "JP1A") (pin "6") (pinfunction "6_6") (pintype "bidirectional"))
    )
    (net (code "55") (name "unconnected-(JP1A-Pad7)") (class "Default")
      (node (ref "JP1A") (pin "7") (pinfunction "7_7") (pintype "bidirectional"))
    )
    (net (code "56") (name "unconnected-(JP1A-Pad8)") (class "Default")
      (node (ref "JP1A") (pin "8") (pinfunction "8_8") (pintype "bidirectional"))
    )
    (net (code "57") (name "unconnected-(JP1A-Pad9)") (class "Default")
      (node (ref "JP1A") (pin "9") (pinfunction "9_9") (pintype "bidirectional"))
    )
    (net (code "58") (name "unconnected-(JP1A-Pad10)") (class "Default")
      (node (ref "JP1A") (pin "10") (pinfunction "10_10") (pintype "bidirectional"))
    )
    (net (code "59") (name "unconnected-(JP1A-Pad11)") (class "Default")
      (node (ref "JP1A") (pin "11") (pinfunction "11_11") (pintype "bidirectional"))
    )
    (net (code "60") (name "unconnected-(JP1A-Pad12)") (class "Default")
      (node (ref "JP1A") (pin "12") (pinfunction "12_12") (pintype "bidirectional"))
    )
    (net (code "61") (name "unconnected-(JP1A-Pad16)") (class "Default")
      (node (ref "JP1A") (pin "16") (pinfunction "16_16") (pintype "bidirectional"))
    )
    (net (code "62") (name "unconnected-(JP1A-Pad18)") (class "Default")
      (node (ref "JP1A") (pin "18") (pinfunction "18_18") (pintype "bidirectional"))
    )
    (net (code "63") (name "unconnected-(JP1A-Pad20)") (class "Default")
      (node (ref "JP1A") (pin "20") (pinfunction "20_20") (pintype "bidirectional"))
    )
    (net (code "64") (name "unconnected-(JP1A-Pad22)") (class "Default")
      (node (ref "JP1A") (pin "22") (pinfunction "22_22") (pintype "bidirectional"))
    )
    (net (code "65") (name "unconnected-(JP1A-Pad24)") (class "Default")
      (node (ref "JP1A") (pin "24") (pinfunction "24_24") (pintype "bidirectional"))
    )
    (net (code "66") (name "unconnected-(JP1A-Pad26)") (class "Default")
      (node (ref "JP1A") (pin "26") (pinfunction "26_26") (pintype "bidirectional"))
    )
    (net (code "67") (name "unconnected-(JP1A-Pad28)") (class "Default")
      (node (ref "JP1A") (pin "28") (pinfunction "28_28") (pintype "bidirectional"))
    )
    (net (code "68") (name "unconnected-(JP1A-Pad30)") (class "Default")
      (node (ref "JP1A") (pin "30") (pinfunction "30_30") (pintype "bidirectional"))
    )
    (net (code "69") (name "unconnected-(JP1A-Pad32)") (class "Default")
      (node (ref "JP1A") (pin "32") (pinfunction "32_32") (pintype "bidirectional"))
    )
    (net (code "70") (name "unconnected-(JP1A-Pad34)") (class "Default")
      (node (ref "JP1A") (pin "34") (pinfunction "34_34") (pintype "bidirectional"))
    )
    (net (code "71") (name "unconnected-(JP1A-Pad35)") (class "Default")
      (node (ref "JP1A") (pin "35") (pinfunction "35_35") (pintype "bidirectional"))
    )
    (net (code "72") (name "unconnected-(JP1A-Pad38)") (class "Default")
      (node (ref "JP1A") (pin "38") (pinfunction "38_38") (pintype "bidirectional"))
    )
    (net (code "73") (name "unconnected-(JP1A-Pad40)") (class "Default")
      (node (ref "JP1A") (pin "40") (pinfunction "40_40") (pintype "bidirectional"))
    )
    (net (code "74") (name "unconnected-(JP1B-Pad1)") (class "Default")
      (node (ref "JP1B") (pin "1") (pinfunction "1_1") (pintype "bidirectional"))
    )
    (net (code "75") (name "unconnected-(JP1B-Pad2)") (class "Default")
      (node (ref "JP1B") (pin "2") (pinfunction "2_2") (pintype "bidirectional"))
    )
    (net (code "76") (name "unconnected-(JP1B-Pad3)") (class "Default")
      (node (ref "JP1B") (pin "3") (pinfunction "3_3") (pintype "bidirectional"))
    )
    (net (code "77") (name "unconnected-(JP1B-Pad4)") (class "Default")
      (node (ref "JP1B") (pin "4") (pinfunction "4_4") (pintype "bidirectional"))
    )
    (net (code "78") (name "unconnected-(JP1B-Pad5)") (class "Default")
      (node (ref "JP1B") (pin "5") (pinfunction "5_5") (pintype "bidirectional"))
    )
    (net (code "79") (name "unconnected-(JP1B-Pad6)") (class "Default")
      (node (ref "JP1B") (pin "6") (pinfunction "6_6") (pintype "bidirectional"))
    )
    (net (code "80") (name "unconnected-(JP1B-Pad7)") (class "Default")
      (node (ref "JP1B") (pin "7") (pinfunction "7_7") (pintype "bidirectional"))
    )
    (net (code "81") (name "unconnected-(JP1B-Pad8)") (class "Default")
      (node (ref "JP1B") (pin "8") (pinfunction "8_8") (pintype "bidirectional"))
    )
    (net (code "82") (name "unconnected-(JP1B-Pad9)") (class "Default")
      (node (ref "JP1B") (pin "9") (pinfunction "9_9") (pintype "bidirectional"))
    )
    (net (code "83") (name "unconnected-(JP1B-Pad10)") (class "Default")
      (node (ref "JP1B") (pin "10") (pinfunction "10_10") (pintype "bidirectional"))
    )
    (net (code "84") (name "unconnected-(JP1B-Pad11)") (class "Default")
      (node (ref "JP1B") (pin "11") (pinfunction "11_11") (pintype "bidirectional"))
    )
    (net (code "85") (name "unconnected-(JP1B-Pad12)") (class "Default")
      (node (ref "JP1B") (pin "12") (pinfunction "12_12") (pintype "bidirectional"))
    )
    (net (code "86") (name "unconnected-(JP1B-Pad13)") (class "Default")
      (node (ref "JP1B") (pin "13") (pinfunction "13_13") (pintype "bidirectional"))
    )
    (net (code "87") (name "unconnected-(JP1B-Pad14)") (class "Default")
      (node (ref "JP1B") (pin "14") (pinfunction "14_14") (pintype "bidirectional"))
    )
    (net (code "88") (name "unconnected-(JP1B-Pad15)") (class "Default")
      (node (ref "JP1B") (pin "15") (pinfunction "15_15") (pintype "bidirectional"))
    )
    (net (code "89") (name "unconnected-(JP1B-Pad17)") (class "Default")
      (node (ref "JP1B") (pin "17") (pinfunction "17_17") (pintype "bidirectional"))
    )
    (net (code "90") (name "unconnected-(JP1B-Pad18)") (class "Default")
      (node (ref "JP1B") (pin "18") (pinfunction "18_18") (pintype "bidirectional"))
    )
    (net (code "91") (name "unconnected-(JP1B-Pad19)") (class "Default")
      (node (ref "JP1B") (pin "19") (pinfunction "19_19") (pintype "bidirectional"))
    )
    (net (code "92") (name "unconnected-(JP1B-Pad20)") (class "Default")
      (node (ref "JP1B") (pin "20") (pinfunction "20_20") (pintype "bidirectional"))
    )
    (net (code "93") (name "unconnected-(JP1B-Pad21)") (class "Default")
      (node (ref "JP1B") (pin "21") (pinfunction "21_21") (pintype "bidirectional"))
    )
    (net (code "94") (name "unconnected-(JP1B-Pad22)") (class "Default")
      (node (ref "JP1B") (pin "22") (pinfunction "22_22") (pintype "bidirectional"))
    )
    (net (code "95") (name "unconnected-(JP1B-Pad23)") (class "Default")
      (node (ref "JP1B") (pin "23") (pinfunction "23_23") (pintype "bidirectional"))
    )
    (net (code "96") (name "unconnected-(JP1B-Pad24)") (class "Default")
      (node (ref "JP1B") (pin "24") (pinfunction "24_24") (pintype "bidirectional"))
    )
    (net (code "97") (name "unconnected-(JP1B-Pad25)") (class "Default")
      (node (ref "JP1B") (pin "25") (pinfunction "25_25") (pintype "bidirectional"))
    )
    (net (code "98") (name "unconnected-(JP1B-Pad26)") (class "Default")
      (node (ref "JP1B") (pin "26") (pinfunction "26_26") (pintype "bidirectional"))
    )
    (net (code "99") (name "unconnected-(JP1B-Pad27)") (class "Default")
      (node (ref "JP1B") (pin "27") (pinfunction "27_27") (pintype "bidirectional"))
    )
    (net (code "100") (name "unconnected-(JP1B-Pad28)") (class "Default")
      (node (ref "JP1B") (pin "28") (pinfunction "28_28") (pintype "bidirectional"))
    )
    (net (code "101") (name "unconnected-(JP1B-Pad29)") (class "Default")
      (node (ref "JP1B") (pin "29") (pinfunction "29_29") (pintype "bidirectional"))
    )
    (net (code "102") (name "unconnected-(JP1B-Pad30)") (class "Default")
      (node (ref "JP1B") (pin "30") (pinfunction "30_30") (pintype "bidirectional"))
    )
    (net (code "103") (name "unconnected-(JP1B-Pad31)") (class "Default")
      (node (ref "JP1B") (pin "31") (pinfunction "31_31") (pintype "bidirectional"))
    )
    (net (code "104") (name "unconnected-(JP1B-Pad32)") (class "Default")
      (node (ref "JP1B") (pin "32") (pinfunction "32_32") (pintype "bidirectional"))
    )
    (net (code "105") (name "unconnected-(JP1B-Pad33)") (class "Default")
      (node (ref "JP1B") (pin "33") (pinfunction "33_33") (pintype "bidirectional"))
    )
    (net (code "106") (name "unconnected-(JP1B-Pad34)") (class "Default")
      (node (ref "JP1B") (pin "34") (pinfunction "34_34") (pintype "bidirectional"))
    )
    (net (code "107") (name "unconnected-(JP1B-Pad35)") (class "Default")
      (node (ref "JP1B") (pin "35") (pinfunction "35_35") (pintype "bidirectional"))
    )
    (net (code "108") (name "unconnected-(JP1B-Pad36)") (class "Default")
      (node (ref "JP1B") (pin "36") (pinfunction "36_36") (pintype "bidirectional"))
    )
    (net (code "109") (name "unconnected-(JP1B-Pad37)") (class "Default")
      (node (ref "JP1B") (pin "37") (pinfunction "37_37") (pintype "bidirectional"))
    )
    (net (code "110") (name "unconnected-(JP1B-Pad39)") (class "Default")
      (node (ref "JP1B") (pin "39") (pinfunction "39_39") (pintype "bidirectional"))
    )
    (net (code "111") (name "unconnected-(JP2A-Pad4)") (class "Default")
      (node (ref "JP2A") (pin "4") (pinfunction "4_4") (pintype "bidirectional"))
    )
    (net (code "112") (name "unconnected-(JP2A-Pad6)") (class "Default")
      (node (ref "JP2A") (pin "6") (pinfunction "6_6") (pintype "bidirectional"))
    )
    (net (code "113") (name "unconnected-(JP2A-Pad7)") (class "Default")
      (node (ref "JP2A") (pin "7") (pinfunction "7_7") (pintype "bidirectional"))
    )
    (net (code "114") (name "unconnected-(JP2A-Pad8)") (class "Default")
      (node (ref "JP2A") (pin "8") (pinfunction "8_8") (pintype "bidirectional"))
    )
    (net (code "115") (name "unconnected-(JP2A-Pad9)") (class "Default")
      (node (ref "JP2A") (pin "9") (pinfunction "9_9") (pintype "bidirectional"))
    )
    (net (code "116") (name "unconnected-(JP2A-Pad10)") (class "Default")
      (node (ref "JP2A") (pin "10") (pinfunction "10_10") (pintype "bidirectional"))
    )
    (net (code "117") (name "unconnected-(JP2A-Pad11)") (class "Default")
      (node (ref "JP2A") (pin "11") (pinfunction "11_11") (pintype "bidirectional"))
    )
    (net (code "118") (name "unconnected-(JP2A-Pad12)") (class "Default")
      (node (ref "JP2A") (pin "12") (pinfunction "12_12") (pintype "bidirectional"))
    )
    (net (code "119") (name "unconnected-(JP2A-Pad13)") (class "Default")
      (node (ref "JP2A") (pin "13") (pinfunction "13_13") (pintype "bidirectional"))
    )
    (net (code "120") (name "unconnected-(JP2A-Pad15)") (class "Default")
      (node (ref "JP2A") (pin "15") (pinfunction "15_15") (pintype "bidirectional"))
    )
    (net (code "121") (name "unconnected-(JP2A-Pad16)") (class "Default")
      (node (ref "JP2A") (pin "16") (pinfunction "16_16") (pintype "bidirectional"))
    )
    (net (code "122") (name "unconnected-(JP2A-Pad17)") (class "Default")
      (node (ref "JP2A") (pin "17") (pinfunction "17_17") (pintype "bidirectional"))
    )
    (net (code "123") (name "unconnected-(JP2A-Pad18)") (class "Default")
      (node (ref "JP2A") (pin "18") (pinfunction "18_18") (pintype "bidirectional"))
    )
    (net (code "124") (name "unconnected-(JP2A-Pad19)") (class "Default")
      (node (ref "JP2A") (pin "19") (pinfunction "19_19") (pintype "bidirectional"))
    )
    (net (code "125") (name "unconnected-(JP2A-Pad20)") (class "Default")
      (node (ref "JP2A") (pin "20") (pinfunction "20_20") (pintype "bidirectional"))
    )
    (net (code "126") (name "unconnected-(JP2A-Pad21)") (class "Default")
      (node (ref "JP2A") (pin "21") (pinfunction "21_21") (pintype "bidirectional"))
    )
    (net (code "127") (name "unconnected-(JP2A-Pad22)") (class "Default")
      (node (ref "JP2A") (pin "22") (pinfunction "22_22") (pintype "bidirectional"))
    )
    (net (code "128") (name "unconnected-(JP2A-Pad23)") (class "Default")
      (node (ref "JP2A") (pin "23") (pinfunction "23_23") (pintype "bidirectional"))
    )
    (net (code "129") (name "unconnected-(JP2A-Pad24)") (class "Default")
      (node (ref "JP2A") (pin "24") (pinfunction "24_24") (pintype "bidirectional"))
    )
    (net (code "130") (name "unconnected-(JP2A-Pad25)") (class "Default")
      (node (ref "JP2A") (pin "25") (pinfunction "25_25") (pintype "bidirectional"))
    )
    (net (code "131") (name "unconnected-(JP2A-Pad26)") (class "Default")
      (node (ref "JP2A") (pin "26") (pinfunction "26_26") (pintype "bidirectional"))
    )
    (net (code "132") (name "unconnected-(JP2A-Pad27)") (class "Default")
      (node (ref "JP2A") (pin "27") (pinfunction "27_27") (pintype "bidirectional"))
    )
    (net (code "133") (name "unconnected-(JP2A-Pad28)") (class "Default")
      (node (ref "JP2A") (pin "28") (pinfunction "28_28") (pintype "bidirectional"))
    )
    (net (code "134") (name "unconnected-(JP2A-Pad29)") (class "Default")
      (node (ref "JP2A") (pin "29") (pinfunction "29_29") (pintype "bidirectional"))
    )
    (net (code "135") (name "unconnected-(JP2A-Pad30)") (class "Default")
      (node (ref "JP2A") (pin "30") (pinfunction "30_30") (pintype "bidirectional"))
    )
    (net (code "136") (name "unconnected-(JP2A-Pad31)") (class "Default")
      (node (ref "JP2A") (pin "31") (pinfunction "31_31") (pintype "bidirectional"))
    )
    (net (code "137") (name "unconnected-(JP2A-Pad32)") (class "Default")
      (node (ref "JP2A") (pin "32") (pinfunction "32_32") (pintype "bidirectional"))
    )
    (net (code "138") (name "unconnected-(JP2A-Pad33)") (class "Default")
      (node (ref "JP2A") (pin "33") (pinfunction "33_33") (pintype "bidirectional"))
    )
    (net (code "139") (name "unconnected-(JP2A-Pad34)") (class "Default")
      (node (ref "JP2A") (pin "34") (pinfunction "34_34") (pintype "bidirectional"))
    )
    (net (code "140") (name "unconnected-(JP2A-Pad36)") (class "Default")
      (node (ref "JP2A") (pin "36") (pinfunction "36_36") (pintype "bidirectional"))
    )
    (net (code "141") (name "unconnected-(JP2A-Pad37)") (class "Default")
      (node (ref "JP2A") (pin "37") (pinfunction "37_37") (pintype "bidirectional"))
    )
    (net (code "142") (name "unconnected-(JP2A-Pad38)") (class "Default")
      (node (ref "JP2A") (pin "38") (pinfunction "38_38") (pintype "bidirectional"))
    )
    (net (code "143") (name "unconnected-(JP2A-Pad39)") (class "Default")
      (node (ref "JP2A") (pin "39") (pinfunction "39_39") (pintype "bidirectional"))
    )
    (net (code "144") (name "unconnected-(JP2A-Pad40)") (class "Default")
      (node (ref "JP2A") (pin "40") (pinfunction "40_40") (pintype "bidirectional"))
    )
    (net (code "145") (name "unconnected-(JP2B-Pad1)") (class "Default")
      (node (ref "JP2B") (pin "1") (pinfunction "1_1") (pintype "bidirectional"))
    )
    (net (code "146") (name "unconnected-(JP2B-Pad2)") (class "Default")
      (node (ref "JP2B") (pin "2") (pinfunction "2_2") (pintype "bidirectional"))
    )
    (net (code "147") (name "unconnected-(JP2B-Pad4)") (class "Default")
      (node (ref "JP2B") (pin "4") (pinfunction "4_4") (pintype "bidirectional"))
    )
    (net (code "148") (name "unconnected-(JP2B-Pad8)") (class "Default")
      (node (ref "JP2B") (pin "8") (pinfunction "8_8") (pintype "bidirectional"))
    )
    (net (code "149") (name "unconnected-(JP2B-Pad9)") (class "Default")
      (node (ref "JP2B") (pin "9") (pinfunction "9_9") (pintype "bidirectional"))
    )
    (net (code "150") (name "unconnected-(JP2B-Pad11)") (class "Default")
      (node (ref "JP2B") (pin "11") (pinfunction "11_11") (pintype "bidirectional"))
    )
    (net (code "151") (name "unconnected-(JP2B-Pad12)") (class "Default")
      (node (ref "JP2B") (pin "12") (pinfunction "12_12") (pintype "bidirectional"))
    )
    (net (code "152") (name "unconnected-(JP2B-Pad13)") (class "Default")
      (node (ref "JP2B") (pin "13") (pinfunction "13_13") (pintype "bidirectional"))
    )
    (net (code "153") (name "unconnected-(JP2B-Pad14)") (class "Default")
      (node (ref "JP2B") (pin "14") (pinfunction "14_14") (pintype "bidirectional"))
    )
    (net (code "154") (name "unconnected-(JP2B-Pad16)") (class "Default")
      (node (ref "JP2B") (pin "16") (pinfunction "16_16") (pintype "bidirectional"))
    )
    (net (code "155") (name "unconnected-(JP2B-Pad19)") (class "Default")
      (node (ref "JP2B") (pin "19") (pinfunction "19_19") (pintype "bidirectional"))
    )
    (net (code "156") (name "unconnected-(JP2B-Pad21)") (class "Default")
      (node (ref "JP2B") (pin "21") (pinfunction "21_21") (pintype "bidirectional"))
    )
    (net (code "157") (name "unconnected-(JP2B-Pad22)") (class "Default")
      (node (ref "JP2B") (pin "22") (pinfunction "22_22") (pintype "bidirectional"))
    )
    (net (code "158") (name "unconnected-(JP2B-Pad24)") (class "Default")
      (node (ref "JP2B") (pin "24") (pinfunction "24_24") (pintype "bidirectional"))
    )
    (net (code "159") (name "unconnected-(JP2B-Pad25)") (class "Default")
      (node (ref "JP2B") (pin "25") (pinfunction "25_25") (pintype "bidirectional"))
    )
    (net (code "160") (name "unconnected-(JP2B-Pad26)") (class "Default")
      (node (ref "JP2B") (pin "26") (pinfunction "26_26") (pintype "bidirectional"))
    )
    (net (code "161") (name "unconnected-(JP2B-Pad27)") (class "Default")
      (node (ref "JP2B") (pin "27") (pinfunction "27_27") (pintype "bidirectional"))
    )
    (net (code "162") (name "unconnected-(JP2B-Pad28)") (class "Default")
      (node (ref "JP2B") (pin "28") (pinfunction "28_28") (pintype "bidirectional"))
    )
    (net (code "163") (name "unconnected-(JP2B-Pad37)") (class "Default")
      (node (ref "JP2B") (pin "37") (pinfunction "37_37") (pintype "bidirectional"))
    )
    (net (code "164") (name "unconnected-(JP2B-Pad39)") (class "Default")
      (node (ref "JP2B") (pin "39") (pinfunction "39_39") (pintype "bidirectional"))
    )
  )
)
